# main_base.net
KiCad netlist of a schematic drawn in Altium Designer
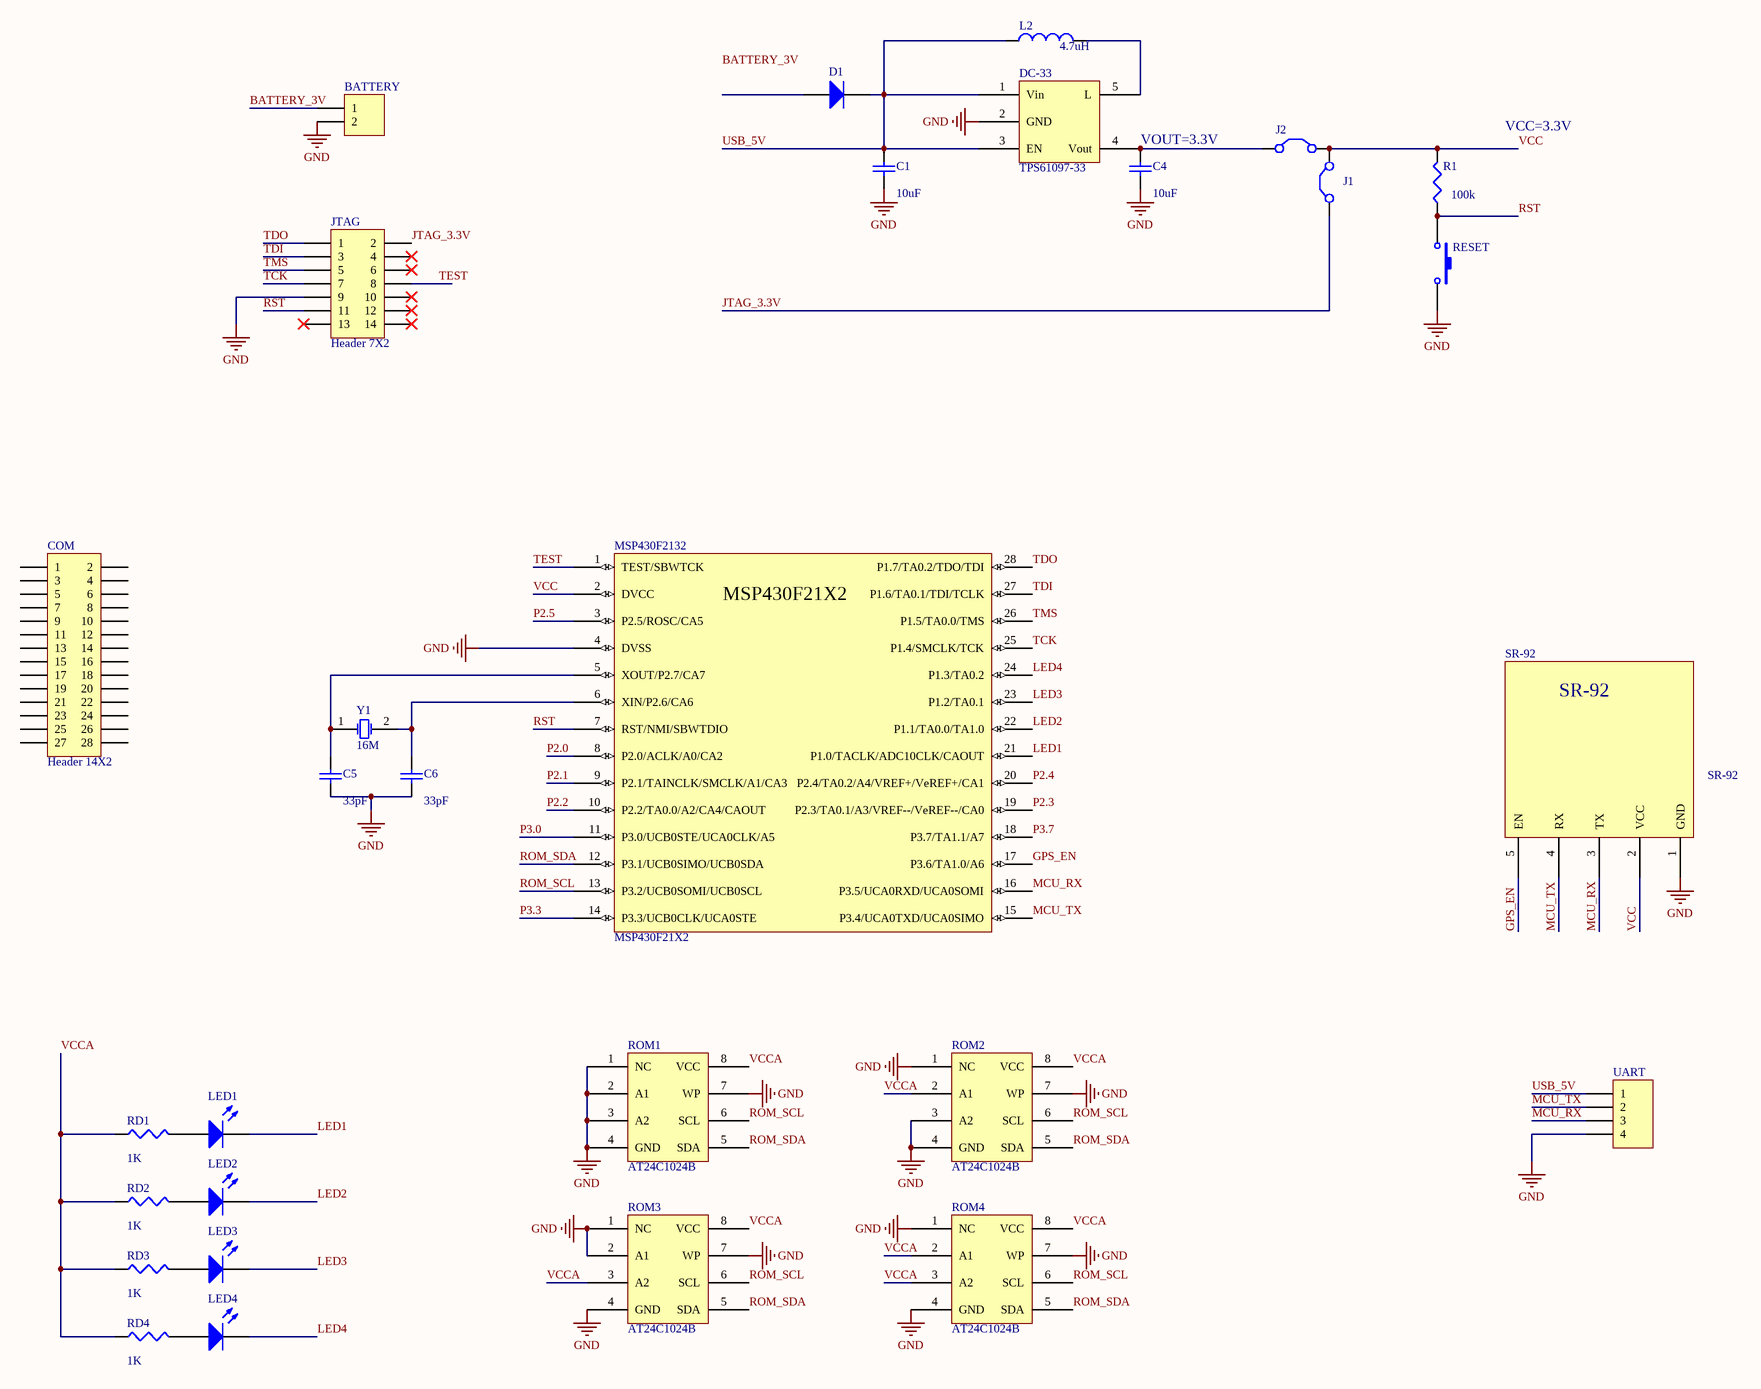
[diagram p0: main_base.SchDoc]

(export (version "E")
  (design (tool "Eeschema 10.0.6"))
  (components
    (comp (ref "BATTERY")
      (value "~")
      (footprint "HDR1X2H")
      (description "Header, 2-Pin, Right Angle")
      (fields (field (name "PUBLISHER") "Altium Limited"))
      (libsource (lib "Miscellaneous Connectors") (part "Header 2H"))
    )
    (comp (ref "C1")
      (value "10uF")
      (footprint "CAPC3216L")
      (description "Capacitor (Semiconductor SIM Model)")
      (fields (field (name "PUBLISHER") "Altium Limited"))
      (libsource (lib "Miscellaneous Devices") (part "Cap Semi"))
    )
    (comp (ref "C4")
      (value "10uF")
      (footprint "CAPC3216L")
      (description "Capacitor (Semiconductor SIM Model)")
      (fields (field (name "PUBLISHER") "Altium Limited"))
      (libsource (lib "Miscellaneous Devices") (part "Cap Semi"))
    )
    (comp (ref "C5")
      (value "33pF")
      (footprint "CAPC3216L")
      (description "Capacitor (Semiconductor SIM Model)")
      (fields (field (name "PUBLISHER") "Altium Limited"))
      (libsource (lib "Miscellaneous Devices") (part "Cap Semi"))
    )
    (comp (ref "C6")
      (value "33pF")
      (footprint "CAPC3216L")
      (description "Capacitor (Semiconductor SIM Model)")
      (fields (field (name "PUBLISHER") "Altium Limited"))
      (libsource (lib "Miscellaneous Devices") (part "Cap Semi"))
    )
    (comp (ref "COM")
      (value "Header 14X2")
      (footprint "HDR2X14")
      (description "Header, 14-Pin, Dual row")
      (fields (field (name "PUBLISHER") "Altium Limited"))
      (libsource (lib "Miscellaneous Connectors") (part "Header 14X2"))
    )
    (comp (ref "D1")
      (value "Switch Diode")
      (footprint "SOT95P240-3N")
      (description "Silicon Low Leakage Diode")
      (fields (field (name "PUBLISHER") "Altium Limited"))
      (libsource (lib "Miscellaneous Devices") (part "Diode BAS116"))
    )
    (comp (ref "DC-33")
      (value "TPS61097-33")
      (footprint "DBV005")
      (libsource (lib "MyLib") (part "TPS61097-33"))
    )
    (comp (ref "J1")
      (value "~")
      (footprint "RAD-0.2")
      (description "Jumper Wire")
      (fields (field (name "PUBLISHER") "Altium Limited"))
      (libsource (lib "Miscellaneous Devices") (part "Jumper"))
    )
    (comp (ref "J2")
      (value "~")
      (footprint "RAD-0.2")
      (description "Jumper Wire")
      (fields (field (name "PUBLISHER") "Altium Limited"))
      (libsource (lib "Miscellaneous Devices") (part "Jumper"))
    )
    (comp (ref "JTAG")
      (value "Header 7X2")
      (footprint "HDR2X7")
      (description "Header, 7-Pin, Dual row")
      (fields (field (name "PUBLISHER") "Altium Limited"))
      (libsource (lib "Miscellaneous Connectors") (part "Header 7X2"))
    )
    (comp (ref "L2")
      (value "4.7uH")
      (footprint "INDC4532L")
      (description "Inductor")
      (fields (field (name "PUBLISHER") "Altium Limited"))
      (libsource (lib "Miscellaneous Devices") (part "Inductor"))
    )
    (comp (ref "LED1")
      (value "LED2")
      (footprint "DSO-F2/D6.1")
      (description "Typical RED, GREEN, YELLOW, AMBER GaAs LED")
      (fields (field (name "PUBLISHER") "Altium Limited"))
      (libsource (lib "Miscellaneous Devices") (part "LED2"))
    )
    (comp (ref "LED2")
      (value "LED2")
      (footprint "DSO-F2/D6.1")
      (description "Typical RED, GREEN, YELLOW, AMBER GaAs LED")
      (fields (field (name "PUBLISHER") "Altium Limited"))
      (libsource (lib "Miscellaneous Devices") (part "LED2"))
    )
    (comp (ref "LED3")
      (value "LED2")
      (footprint "DSO-F2/D6.1")
      (description "Typical RED, GREEN, YELLOW, AMBER GaAs LED")
      (fields (field (name "PUBLISHER") "Altium Limited"))
      (libsource (lib "Miscellaneous Devices") (part "LED2"))
    )
    (comp (ref "LED4")
      (value "LED2")
      (footprint "DSO-F2/D6.1")
      (description "Typical RED, GREEN, YELLOW, AMBER GaAs LED")
      (fields (field (name "PUBLISHER") "Altium Limited"))
      (libsource (lib "Miscellaneous Devices") (part "LED2"))
    )
    (comp (ref "MSP430F2132")
      (value "MSP430F21X2")
      (footprint "PW028")
      (libsource (lib "TI Microcontroller 16-Bit MSP430") (part "MSP430F21X2"))
    )
    (comp (ref "R1")
      (value "100k")
      (footprint "RESC1608L")
      (description "Resistor")
      (fields (field (name "PUBLISHER") "Altium Limited"))
      (libsource (lib "Miscellaneous Devices") (part "Res3"))
    )
    (comp (ref "RD1")
      (value "1K")
      (footprint "RESC1608L")
      (description "Resistor")
      (fields (field (name "PUBLISHER") "Altium Limited"))
      (libsource (lib "Miscellaneous Devices") (part "Res3"))
    )
    (comp (ref "RD2")
      (value "1K")
      (footprint "RESC1608L")
      (description "Resistor")
      (fields (field (name "PUBLISHER") "Altium Limited"))
      (libsource (lib "Miscellaneous Devices") (part "Res3"))
    )
    (comp (ref "RD3")
      (value "1K")
      (footprint "RESC1608L")
      (description "Resistor")
      (fields (field (name "PUBLISHER") "Altium Limited"))
      (libsource (lib "Miscellaneous Devices") (part "Res3"))
    )
    (comp (ref "RD4")
      (value "1K")
      (footprint "RESC1608L")
      (description "Resistor")
      (fields (field (name "PUBLISHER") "Altium Limited"))
      (libsource (lib "Miscellaneous Devices") (part "Res3"))
    )
    (comp (ref "RESET")
      (value "~")
      (footprint "SPST-2")
      (description "Switch")
      (fields (field (name "PUBLISHER") "Altium Limited"))
      (libsource (lib "Miscellaneous Devices") (part "SW-PB"))
    )
    (comp (ref "ROM1") (value "AT24C1024B") (footprint "8S2_M") (libsource (lib "MyLib") (part "AT24C1024B")))
    (comp (ref "ROM2") (value "AT24C1024B") (footprint "8S2_M") (libsource (lib "MyLib") (part "AT24C1024B")))
    (comp (ref "ROM3") (value "AT24C1024B") (footprint "8S2_M") (libsource (lib "MyLib") (part "AT24C1024B")))
    (comp (ref "ROM4") (value "AT24C1024B") (footprint "8S2_M") (libsource (lib "MyLib") (part "AT24C1024B")))
    (comp (ref "SR-92") (value "SR-92") (footprint "HDR1X5") (libsource (lib "MyLib") (part "SR-92")))
    (comp (ref "UART")
      (value "~")
      (footprint "HDR1X4H")
      (description "Header, 4-Pin, Right Angle")
      (fields (field (name "PUBLISHER") "Altium Limited"))
      (libsource (lib "Miscellaneous Connectors") (part "Header 4H"))
    )
    (comp (ref "Y1")
      (value "16M")
      (footprint "BCY-W2/D3.1")
      (description "Crystal Oscillator")
      (fields (field (name "PUBLISHER") "Altium Limited"))
      (libsource (lib "Miscellaneous Devices") (part "XTAL"))
    )
  )
  (nets
    (net (code "1") (name "/BATTERY_3V") (class "Default")
      (node (ref "BATTERY") (pin "1") (pinfunction "1_1") (pintype "passive"))
    )
    (net (code "2") (name "/GPS_EN") (class "Default")
      (node (ref "MSP430F2132") (pin "17") (pinfunction "P3.6/TA1.0/A6_17") (pintype "bidirectional"))
      (node (ref "SR-92") (pin "5") (pinfunction "EN_5") (pintype "passive"))
    )
    (net (code "3") (name "/JTAG_3.3V") (class "Default")
      (node (ref "J1") (pin "1") (pinfunction "C1_1") (pintype "passive"))
      (node (ref "JTAG") (pin "2") (pinfunction "2_2") (pintype "passive"))
    )
    (net (code "4") (name "/LED1") (class "Default")
      (node (ref "LED1") (pin "2") (pinfunction "K_2") (pintype "passive"))
      (node (ref "MSP430F2132") (pin "21") (pinfunction "P1.0/TACLK/ADC10CLK/CAOUT_21") (pintype "bidirectional"))
    )
    (net (code "5") (name "/LED2") (class "Default")
      (node (ref "LED2") (pin "2") (pinfunction "K_2") (pintype "passive"))
      (node (ref "MSP430F2132") (pin "22") (pinfunction "P1.1/TA0.0/TA1.0_22") (pintype "bidirectional"))
    )
    (net (code "6") (name "/LED3") (class "Default")
      (node (ref "LED3") (pin "2") (pinfunction "K_2") (pintype "passive"))
      (node (ref "MSP430F2132") (pin "23") (pinfunction "P1.2/TA0.1_23") (pintype "bidirectional"))
    )
    (net (code "7") (name "/LED4") (class "Default")
      (node (ref "LED4") (pin "2") (pinfunction "K_2") (pintype "passive"))
      (node (ref "MSP430F2132") (pin "24") (pinfunction "P1.3/TA0.2_24") (pintype "bidirectional"))
    )
    (net (code "8") (name "/MCU_RX") (class "Default")
      (node (ref "MSP430F2132") (pin "16") (pinfunction "P3.5/UCA0RXD/UCA0SOMI_16") (pintype "bidirectional"))
      (node (ref "SR-92") (pin "3") (pinfunction "TX_3") (pintype "passive"))
      (node (ref "UART") (pin "3") (pinfunction "3_3") (pintype "passive"))
    )
    (net (code "9") (name "/MCU_TX") (class "Default")
      (node (ref "MSP430F2132") (pin "15") (pinfunction "P3.4/UCA0TXD/UCA0SIMO_15") (pintype "bidirectional"))
      (node (ref "SR-92") (pin "4") (pinfunction "RX_4") (pintype "passive"))
      (node (ref "UART") (pin "2") (pinfunction "2_2") (pintype "passive"))
    )
    (net (code "10") (name "/P2.0") (class "Default")
      (node (ref "MSP430F2132") (pin "8") (pinfunction "P2.0/ACLK/A0/CA2_8") (pintype "bidirectional"))
    )
    (net (code "11") (name "/P2.1") (class "Default")
      (node (ref "MSP430F2132") (pin "9") (pinfunction "P2.1/TAINCLK/SMCLK/A1/CA3_9") (pintype "bidirectional"))
    )
    (net (code "12") (name "/P2.2") (class "Default")
      (node (ref "MSP430F2132") (pin "10") (pinfunction "P2.2/TA0.0/A2/CA4/CAOUT_10") (pintype "bidirectional"))
    )
    (net (code "13") (name "/P2.3") (class "Default")
      (node (ref "MSP430F2132") (pin "19") (pinfunction "P2.3/TA0.1/A3/VREF--/VeREF--/CA0_19") (pintype "bidirectional"))
    )
    (net (code "14") (name "/P2.4") (class "Default")
      (node (ref "MSP430F2132") (pin "20") (pinfunction "P2.4/TA0.2/A4/VREF+/VeREF+/CA1_20") (pintype "bidirectional"))
    )
    (net (code "15") (name "/P2.5") (class "Default")
      (node (ref "MSP430F2132") (pin "3") (pinfunction "P2.5/ROSC/CA5_3") (pintype "bidirectional"))
    )
    (net (code "16") (name "/P3.0") (class "Default")
      (node (ref "MSP430F2132") (pin "11") (pinfunction "P3.0/UCB0STE/UCA0CLK/A5_11") (pintype "bidirectional"))
    )
    (net (code "17") (name "/P3.3") (class "Default")
      (node (ref "MSP430F2132") (pin "14") (pinfunction "P3.3/UCB0CLK/UCA0STE_14") (pintype "bidirectional"))
    )
    (net (code "18") (name "/P3.7") (class "Default")
      (node (ref "MSP430F2132") (pin "18") (pinfunction "P3.7/TA1.1/A7_18") (pintype "bidirectional"))
    )
    (net (code "19") (name "/ROM_SCL") (class "Default")
      (node (ref "MSP430F2132") (pin "13") (pinfunction "P3.2/UCB0SOMI/UCB0SCL_13") (pintype "bidirectional"))
      (node (ref "ROM1") (pin "6") (pinfunction "SCL_6") (pintype "passive"))
      (node (ref "ROM2") (pin "6") (pinfunction "SCL_6") (pintype "passive"))
      (node (ref "ROM3") (pin "6") (pinfunction "SCL_6") (pintype "passive"))
      (node (ref "ROM4") (pin "6") (pinfunction "SCL_6") (pintype "passive"))
    )
    (net (code "20") (name "/ROM_SDA") (class "Default")
      (node (ref "MSP430F2132") (pin "12") (pinfunction "P3.1/UCB0SIMO/UCB0SDA_12") (pintype "bidirectional"))
      (node (ref "ROM1") (pin "5") (pinfunction "SDA_5") (pintype "passive"))
      (node (ref "ROM2") (pin "5") (pinfunction "SDA_5") (pintype "passive"))
      (node (ref "ROM3") (pin "5") (pinfunction "SDA_5") (pintype "passive"))
      (node (ref "ROM4") (pin "5") (pinfunction "SDA_5") (pintype "passive"))
    )
    (net (code "21") (name "/RST") (class "Default")
      (node (ref "JTAG") (pin "11") (pinfunction "11_11") (pintype "passive"))
      (node (ref "MSP430F2132") (pin "7") (pinfunction "RST/NMI/SBWTDIO_7") (pintype "bidirectional"))
      (node (ref "R1") (pin "1") (pinfunction "1_1") (pintype "passive"))
      (node (ref "RESET") (pin "1") (pinfunction "1_1") (pintype "passive"))
    )
    (net (code "22") (name "/TCK") (class "Default")
      (node (ref "JTAG") (pin "7") (pinfunction "7_7") (pintype "passive"))
      (node (ref "MSP430F2132") (pin "25") (pinfunction "P1.4/SMCLK/TCK_25") (pintype "bidirectional"))
    )
    (net (code "23") (name "/TDI") (class "Default")
      (node (ref "JTAG") (pin "3") (pinfunction "3_3") (pintype "passive"))
      (node (ref "MSP430F2132") (pin "27") (pinfunction "P1.6/TA0.1/TDI/TCLK_27") (pintype "bidirectional"))
    )
    (net (code "24") (name "/TDO") (class "Default")
      (node (ref "JTAG") (pin "1") (pinfunction "1_1") (pintype "passive"))
      (node (ref "MSP430F2132") (pin "28") (pinfunction "P1.7/TA0.2/TDO/TDI_28") (pintype "bidirectional"))
    )
    (net (code "25") (name "/TEST") (class "Default")
      (node (ref "JTAG") (pin "8") (pinfunction "8_8") (pintype "passive"))
      (node (ref "MSP430F2132") (pin "1") (pinfunction "TEST/SBWTCK_1") (pintype "bidirectional"))
    )
    (net (code "26") (name "/TMS") (class "Default")
      (node (ref "JTAG") (pin "5") (pinfunction "5_5") (pintype "passive"))
      (node (ref "MSP430F2132") (pin "26") (pinfunction "P1.5/TA0.0/TMS_26") (pintype "bidirectional"))
    )
    (net (code "27") (name "/USB_5V") (class "Default")
      (node (ref "C1") (pin "2") (pinfunction "2_2") (pintype "passive"))
      (node (ref "D1") (pin "3") (pinfunction "K_3") (pintype "passive"))
      (node (ref "DC-33") (pin "1") (pinfunction "Vin_1") (pintype "passive"))
      (node (ref "DC-33") (pin "3") (pinfunction "EN_3") (pintype "passive"))
      (node (ref "L2") (pin "1") (pinfunction "1_1") (pintype "passive"))
      (node (ref "UART") (pin "1") (pinfunction "1_1") (pintype "passive"))
    )
    (net (code "28") (name "/VCC") (class "Default")
      (node (ref "J1") (pin "2") (pinfunction "C2_2") (pintype "passive"))
      (node (ref "J2") (pin "2") (pinfunction "C2_2") (pintype "passive"))
      (node (ref "MSP430F2132") (pin "2") (pinfunction "DVCC_2") (pintype "bidirectional"))
      (node (ref "R1") (pin "2") (pinfunction "2_2") (pintype "passive"))
      (node (ref "SR-92") (pin "2") (pinfunction "VCC_2") (pintype "passive"))
    )
    (net (code "29") (name "/VCCA") (class "Default")
      (node (ref "RD1") (pin "1") (pinfunction "1_1") (pintype "passive"))
      (node (ref "RD2") (pin "1") (pinfunction "1_1") (pintype "passive"))
      (node (ref "RD3") (pin "1") (pinfunction "1_1") (pintype "passive"))
      (node (ref "RD4") (pin "1") (pinfunction "1_1") (pintype "passive"))
      (node (ref "ROM1") (pin "8") (pinfunction "VCC_8") (pintype "passive"))
      (node (ref "ROM2") (pin "2") (pinfunction "A1_2") (pintype "passive"))
      (node (ref "ROM2") (pin "8") (pinfunction "VCC_8") (pintype "passive"))
      (node (ref "ROM3") (pin "3") (pinfunction "A2_3") (pintype "passive"))
      (node (ref "ROM3") (pin "8") (pinfunction "VCC_8") (pintype "passive"))
      (node (ref "ROM4") (pin "2") (pinfunction "A1_2") (pintype "passive"))
      (node (ref "ROM4") (pin "3") (pinfunction "A2_3") (pintype "passive"))
      (node (ref "ROM4") (pin "8") (pinfunction "VCC_8") (pintype "passive"))
    )
    (net (code "30") (name "GND") (class "Default")
      (node (ref "BATTERY") (pin "2") (pinfunction "2_2") (pintype "passive"))
      (node (ref "C1") (pin "1") (pinfunction "1_1") (pintype "passive"))
      (node (ref "C4") (pin "1") (pinfunction "1_1") (pintype "passive"))
      (node (ref "C5") (pin "1") (pinfunction "1_1") (pintype "passive"))
      (node (ref "C6") (pin "1") (pinfunction "1_1") (pintype "passive"))
      (node (ref "DC-33") (pin "2") (pinfunction "GND_2") (pintype "passive"))
      (node (ref "JTAG") (pin "9") (pinfunction "9_9") (pintype "passive"))
      (node (ref "MSP430F2132") (pin "4") (pinfunction "DVSS_4") (pintype "bidirectional"))
      (node (ref "RESET") (pin "2") (pinfunction "2_2") (pintype "passive"))
      (node (ref "ROM1") (pin "1") (pinfunction "NC_1") (pintype "passive"))
      (node (ref "ROM1") (pin "2") (pinfunction "A1_2") (pintype "passive"))
      (node (ref "ROM1") (pin "3") (pinfunction "A2_3") (pintype "passive"))
      (node (ref "ROM1") (pin "4") (pinfunction "GND_4") (pintype "passive"))
      (node (ref "ROM1") (pin "7") (pinfunction "WP_7") (pintype "passive"))
      (node (ref "ROM2") (pin "1") (pinfunction "NC_1") (pintype "passive"))
      (node (ref "ROM2") (pin "3") (pinfunction "A2_3") (pintype "passive"))
      (node (ref "ROM2") (pin "4") (pinfunction "GND_4") (pintype "passive"))
      (node (ref "ROM2") (pin "7") (pinfunction "WP_7") (pintype "passive"))
      (node (ref "ROM3") (pin "1") (pinfunction "NC_1") (pintype "passive"))
      (node (ref "ROM3") (pin "2") (pinfunction "A1_2") (pintype "passive"))
      (node (ref "ROM3") (pin "4") (pinfunction "GND_4") (pintype "passive"))
      (node (ref "ROM3") (pin "7") (pinfunction "WP_7") (pintype "passive"))
      (node (ref "ROM4") (pin "1") (pinfunction "NC_1") (pintype "passive"))
      (node (ref "ROM4") (pin "4") (pinfunction "GND_4") (pintype "passive"))
      (node (ref "ROM4") (pin "7") (pinfunction "WP_7") (pintype "passive"))
      (node (ref "SR-92") (pin "1") (pinfunction "GND_1") (pintype "passive"))
      (node (ref "UART") (pin "4") (pinfunction "4_4") (pintype "passive"))
    )
    (net (code "31") (name "Net-(DC-33-L)") (class "Default")
      (node (ref "DC-33") (pin "5") (pinfunction "L_5") (pintype "passive"))
      (node (ref "L2") (pin "2") (pinfunction "2_2") (pintype "passive"))
    )
    (net (code "32") (name "Net-(DC-33-Vout)") (class "Default")
      (node (ref "C4") (pin "2") (pinfunction "2_2") (pintype "passive"))
      (node (ref "DC-33") (pin "4") (pinfunction "Vout_4") (pintype "passive"))
      (node (ref "J2") (pin "1") (pinfunction "C1_1") (pintype "passive"))
    )
    (net (code "33") (name "Net-(LED1-A)") (class "Default")
      (node (ref "LED1") (pin "1") (pinfunction "A_1") (pintype "passive"))
      (node (ref "RD1") (pin "2") (pinfunction "2_2") (pintype "passive"))
    )
    (net (code "34") (name "Net-(LED2-A)") (class "Default")
      (node (ref "LED2") (pin "1") (pinfunction "A_1") (pintype "passive"))
      (node (ref "RD2") (pin "2") (pinfunction "2_2") (pintype "passive"))
    )
    (net (code "35") (name "Net-(LED3-A)") (class "Default")
      (node (ref "LED3") (pin "1") (pinfunction "A_1") (pintype "passive"))
      (node (ref "RD3") (pin "2") (pinfunction "2_2") (pintype "passive"))
    )
    (net (code "36") (name "Net-(LED4-A)") (class "Default")
      (node (ref "LED4") (pin "1") (pinfunction "A_1") (pintype "passive"))
      (node (ref "RD4") (pin "2") (pinfunction "2_2") (pintype "passive"))
    )
    (net (code "37") (name "Net-(MSP430F2132-XIN{slash}P2.6{slash}CA6)") (class "Default")
      (node (ref "C6") (pin "2") (pinfunction "2_2") (pintype "passive"))
      (node (ref "MSP430F2132") (pin "6") (pinfunction "XIN/P2.6/CA6_6") (pintype "bidirectional"))
      (node (ref "Y1") (pin "2") (pinfunction "OSC2_2") (pintype "passive"))
    )
    (net (code "38") (name "Net-(MSP430F2132-XOUT{slash}P2.7{slash}CA7)") (class "Default")
      (node (ref "C5") (pin "2") (pinfunction "2_2") (pintype "passive"))
      (node (ref "MSP430F2132") (pin "5") (pinfunction "XOUT/P2.7/CA7_5") (pintype "bidirectional"))
      (node (ref "Y1") (pin "1") (pinfunction "OSC1_1") (pintype "passive"))
    )
    (net (code "39") (name "unconnected-(COM-Pad1)") (class "Default")
      (node (ref "COM") (pin "1") (pinfunction "1_1") (pintype "passive"))
    )
    (net (code "40") (name "unconnected-(COM-Pad2)") (class "Default")
      (node (ref "COM") (pin "2") (pinfunction "2_2") (pintype "passive"))
    )
    (net (code "41") (name "unconnected-(COM-Pad3)") (class "Default")
      (node (ref "COM") (pin "3") (pinfunction "3_3") (pintype "passive"))
    )
    (net (code "42") (name "unconnected-(COM-Pad4)") (class "Default")
      (node (ref "COM") (pin "4") (pinfunction "4_4") (pintype "passive"))
    )
    (net (code "43") (name "unconnected-(COM-Pad5)") (class "Default")
      (node (ref "COM") (pin "5") (pinfunction "5_5") (pintype "passive"))
    )
    (net (code "44") (name "unconnected-(COM-Pad6)") (class "Default")
      (node (ref "COM") (pin "6") (pinfunction "6_6") (pintype "passive"))
    )
    (net (code "45") (name "unconnected-(COM-Pad7)") (class "Default")
      (node (ref "COM") (pin "7") (pinfunction "7_7") (pintype "passive"))
    )
    (net (code "46") (name "unconnected-(COM-Pad8)") (class "Default")
      (node (ref "COM") (pin "8") (pinfunction "8_8") (pintype "passive"))
    )
    (net (code "47") (name "unconnected-(COM-Pad9)") (class "Default")
      (node (ref "COM") (pin "9") (pinfunction "9_9") (pintype "passive"))
    )
    (net (code "48") (name "unconnected-(COM-Pad10)") (class "Default")
      (node (ref "COM") (pin "10") (pinfunction "10_10") (pintype "passive"))
    )
    (net (code "49") (name "unconnected-(COM-Pad11)") (class "Default")
      (node (ref "COM") (pin "11") (pinfunction "11_11") (pintype "passive"))
    )
    (net (code "50") (name "unconnected-(COM-Pad12)") (class "Default")
      (node (ref "COM") (pin "12") (pinfunction "12_12") (pintype "passive"))
    )
    (net (code "51") (name "unconnected-(COM-Pad13)") (class "Default")
      (node (ref "COM") (pin "13") (pinfunction "13_13") (pintype "passive"))
    )
    (net (code "52") (name "unconnected-(COM-Pad14)") (class "Default")
      (node (ref "COM") (pin "14") (pinfunction "14_14") (pintype "passive"))
    )
    (net (code "53") (name "unconnected-(COM-Pad15)") (class "Default")
      (node (ref "COM") (pin "15") (pinfunction "15_15") (pintype "passive"))
    )
    (net (code "54") (name "unconnected-(COM-Pad16)") (class "Default")
      (node (ref "COM") (pin "16") (pinfunction "16_16") (pintype "passive"))
    )
    (net (code "55") (name "unconnected-(COM-Pad17)") (class "Default")
      (node (ref "COM") (pin "17") (pinfunction "17_17") (pintype "passive"))
    )
    (net (code "56") (name "unconnected-(COM-Pad18)") (class "Default")
      (node (ref "COM") (pin "18") (pinfunction "18_18") (pintype "passive"))
    )
    (net (code "57") (name "unconnected-(COM-Pad19)") (class "Default")
      (node (ref "COM") (pin "19") (pinfunction "19_19") (pintype "passive"))
    )
    (net (code "58") (name "unconnected-(COM-Pad20)") (class "Default")
      (node (ref "COM") (pin "20") (pinfunction "20_20") (pintype "passive"))
    )
    (net (code "59") (name "unconnected-(COM-Pad21)") (class "Default")
      (node (ref "COM") (pin "21") (pinfunction "21_21") (pintype "passive"))
    )
    (net (code "60") (name "unconnected-(COM-Pad22)") (class "Default")
      (node (ref "COM") (pin "22") (pinfunction "22_22") (pintype "passive"))
    )
    (net (code "61") (name "unconnected-(COM-Pad23)") (class "Default")
      (node (ref "COM") (pin "23") (pinfunction "23_23") (pintype "passive"))
    )
    (net (code "62") (name "unconnected-(COM-Pad24)") (class "Default")
      (node (ref "COM") (pin "24") (pinfunction "24_24") (pintype "passive"))
    )
    (net (code "63") (name "unconnected-(COM-Pad25)") (class "Default")
      (node (ref "COM") (pin "25") (pinfunction "25_25") (pintype "passive"))
    )
    (net (code "64") (name "unconnected-(COM-Pad26)") (class "Default")
      (node (ref "COM") (pin "26") (pinfunction "26_26") (pintype "passive"))
    )
    (net (code "65") (name "unconnected-(COM-Pad27)") (class "Default")
      (node (ref "COM") (pin "27") (pinfunction "27_27") (pintype "passive"))
    )
    (net (code "66") (name "unconnected-(COM-Pad28)") (class "Default")
      (node (ref "COM") (pin "28") (pinfunction "28_28") (pintype "passive"))
    )
    (net (code "67") (name "unconnected-(D1-A-Pad1)") (class "Default")
      (node (ref "D1") (pin "1") (pinfunction "A_1") (pintype "passive"))
    )
    (net (code "68") (name "unconnected-(JTAG-Pad4)") (class "Default")
      (node (ref "JTAG") (pin "4") (pinfunction "4_4") (pintype "passive+no_connect"))
    )
    (net (code "69") (name "unconnected-(JTAG-Pad6)") (class "Default")
      (node (ref "JTAG") (pin "6") (pinfunction "6_6") (pintype "passive+no_connect"))
    )
    (net (code "70") (name "unconnected-(JTAG-Pad10)") (class "Default")
      (node (ref "JTAG") (pin "10") (pinfunction "10_10") (pintype "passive+no_connect"))
    )
    (net (code "71") (name "unconnected-(JTAG-Pad12)") (class "Default")
      (node (ref "JTAG") (pin "12") (pinfunction "12_12") (pintype "passive+no_connect"))
    )
    (net (code "72") (name "unconnected-(JTAG-Pad13)") (class "Default")
      (node (ref "JTAG") (pin "13") (pinfunction "13_13") (pintype "passive+no_connect"))
    )
    (net (code "73") (name "unconnected-(JTAG-Pad14)") (class "Default")
      (node (ref "JTAG") (pin "14") (pinfunction "14_14") (pintype "passive+no_connect"))
    )
  )
)
